# Serial_Gauge_V0_1.net
KiCad netlist of a schematic drawn in EAGLE
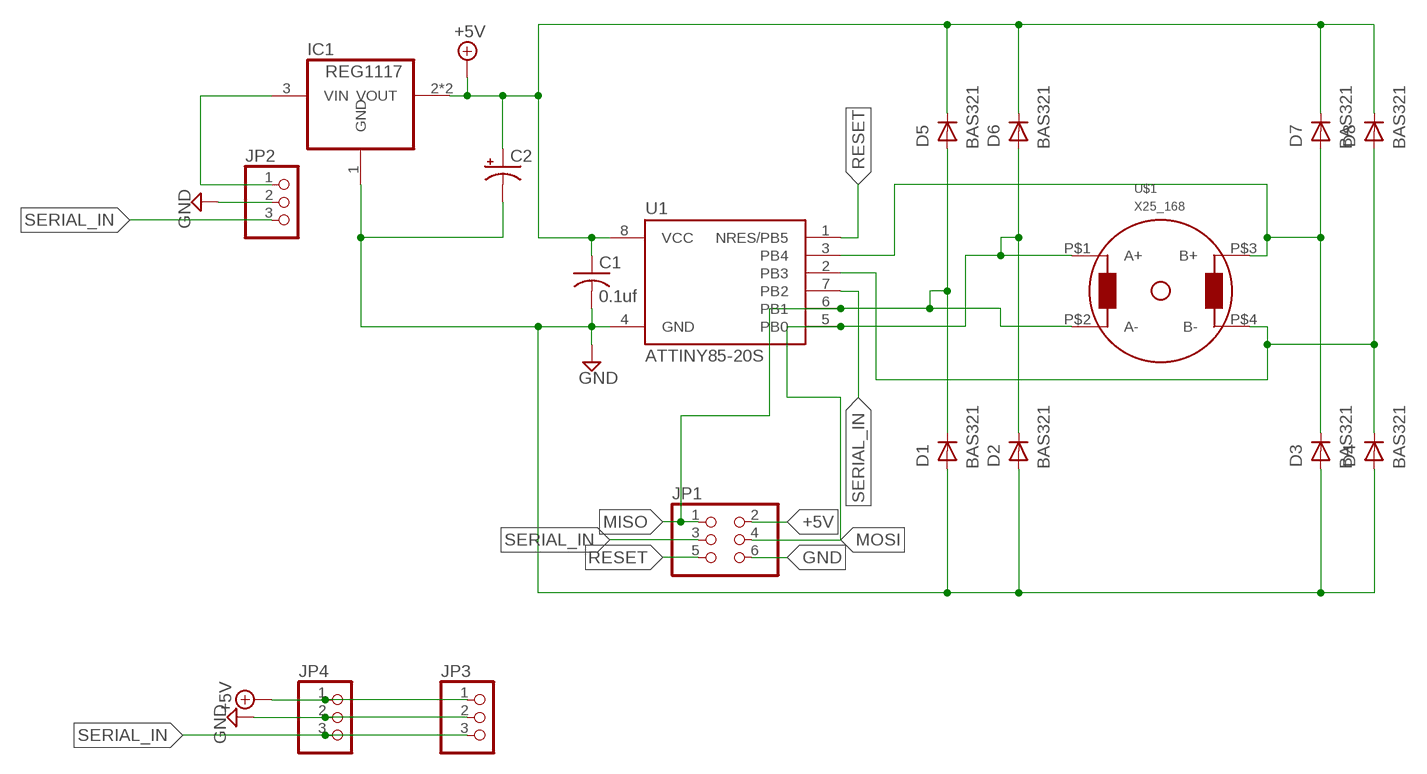
[diagram p0: schematic, sheet 1]

(export (version "E")
  (design (tool "Eeschema 10.0.6"))
  (components
    (comp (ref "C1")
      (value "0.1uf")
      (footprint "eagle-import:C1206K")
      (libsource (lib "eagle-import") (part "C-USC1206K"))
    )
    (comp (ref "C2")
      (value "CPOL-US140CLH-0810")
      (footprint "eagle-import:140CLH-0810")
      (libsource (lib "eagle-import") (part "CPOL-US140CLH-0810"))
    )
    (comp (ref "D1")
      (value "BAS321")
      (footprint "eagle-import:SOD323(F)")
      (libsource (lib "eagle-import") (part "BAS321"))
    )
    (comp (ref "D2")
      (value "BAS321")
      (footprint "eagle-import:SOD323(F)")
      (libsource (lib "eagle-import") (part "BAS321"))
    )
    (comp (ref "D3")
      (value "BAS321")
      (footprint "eagle-import:SOD323(F)")
      (libsource (lib "eagle-import") (part "BAS321"))
    )
    (comp (ref "D4")
      (value "BAS321")
      (footprint "eagle-import:SOD323(F)")
      (libsource (lib "eagle-import") (part "BAS321"))
    )
    (comp (ref "D5")
      (value "BAS321")
      (footprint "eagle-import:SOD323(F)")
      (libsource (lib "eagle-import") (part "BAS321"))
    )
    (comp (ref "D6")
      (value "BAS321")
      (footprint "eagle-import:SOD323(F)")
      (libsource (lib "eagle-import") (part "BAS321"))
    )
    (comp (ref "D7")
      (value "BAS321")
      (footprint "eagle-import:SOD323(F)")
      (libsource (lib "eagle-import") (part "BAS321"))
    )
    (comp (ref "D8")
      (value "BAS321")
      (footprint "eagle-import:SOD323(F)")
      (libsource (lib "eagle-import") (part "BAS321"))
    )
    (comp (ref "IC1")
      (value "REG1117")
      (footprint "eagle-import:SOT223")
      (libsource (lib "eagle-import") (part "REG1117"))
    )
    (comp (ref "JP1")
      (value "PINHD-2X3")
      (footprint "eagle-import:2X03")
      (libsource (lib "eagle-import") (part "PINHD-2X3"))
    )
    (comp (ref "JP2")
      (value "PINHD-1X3")
      (footprint "eagle-import:1X03")
      (libsource (lib "eagle-import") (part "PINHD-1X3"))
    )
    (comp (ref "JP3")
      (value "PINHD-1X3")
      (footprint "eagle-import:1X03")
      (libsource (lib "eagle-import") (part "PINHD-1X3"))
    )
    (comp (ref "JP4")
      (value "PINHD-1X3")
      (footprint "eagle-import:1X03")
      (libsource (lib "eagle-import") (part "PINHD-1X3"))
    )
    (comp (ref "U$1")
      (value "X25_168")
      (footprint "eagle-import:X25_168")
      (libsource (lib "eagle-import") (part "X25_168"))
    )
    (comp (ref "U1")
      (value "ATTINY85-20S")
      (footprint "eagle-import:SOIC8_EIAJ_208MIL")
      (libsource (lib "eagle-import") (part "ATTINY85S-20"))
    )
  )
  (nets
    (net (code "1") (name "+5V") (class "Default")
      (node (ref "C1") (pin "1") (pinfunction "1_1") (pintype "passive"))
      (node (ref "C2") (pin "+") (pinfunction "+_+") (pintype "passive"))
      (node (ref "D5") (pin "1") (pinfunction "K_1") (pintype "passive"))
      (node (ref "D6") (pin "1") (pinfunction "K_1") (pintype "passive"))
      (node (ref "D7") (pin "1") (pinfunction "K_1") (pintype "passive"))
      (node (ref "D8") (pin "1") (pinfunction "K_1") (pintype "passive"))
      (node (ref "IC1") (pin "2") (pinfunction "VOUT_2") (pintype "output"))
      (node (ref "IC1") (pin "4") (pinfunction "VOUT_4") (pintype "output"))
      (node (ref "JP1") (pin "2") (pinfunction "2_2") (pintype "passive"))
      (node (ref "JP3") (pin "1") (pinfunction "1_1") (pintype "passive"))
      (node (ref "JP4") (pin "1") (pinfunction "1_1") (pintype "passive"))
      (node (ref "U1") (pin "8") (pinfunction "VCC_8") (pintype "power_in"))
    )
    (net (code "2") (name "GND") (class "Default")
      (node (ref "C1") (pin "2") (pinfunction "2_2") (pintype "passive"))
      (node (ref "C2") (pin "-") (pinfunction "-_-") (pintype "passive"))
      (node (ref "D1") (pin "2") (pinfunction "A_2") (pintype "passive"))
      (node (ref "D2") (pin "2") (pinfunction "A_2") (pintype "passive"))
      (node (ref "D3") (pin "2") (pinfunction "A_2") (pintype "passive"))
      (node (ref "D4") (pin "2") (pinfunction "A_2") (pintype "passive"))
      (node (ref "IC1") (pin "1") (pinfunction "GND_1") (pintype "power_in"))
      (node (ref "JP1") (pin "6") (pinfunction "6_6") (pintype "passive"))
      (node (ref "JP2") (pin "2") (pinfunction "2_2") (pintype "passive"))
      (node (ref "JP3") (pin "2") (pinfunction "2_2") (pintype "passive"))
      (node (ref "JP4") (pin "2") (pinfunction "2_2") (pintype "passive"))
      (node (ref "U1") (pin "4") (pinfunction "GND_4") (pintype "power_in"))
    )
    (net (code "3") (name "MISO") (class "Default")
      (node (ref "D1") (pin "1") (pinfunction "K_1") (pintype "passive"))
      (node (ref "D5") (pin "2") (pinfunction "A_2") (pintype "passive"))
      (node (ref "JP1") (pin "1") (pinfunction "1_1") (pintype "passive"))
      (node (ref "U$1") (pin "P$2") (pinfunction "A-_P$2") (pintype "input"))
      (node (ref "U1") (pin "6") (pinfunction "PB1_6") (pintype "bidirectional"))
    )
    (net (code "4") (name "MOSI") (class "Default")
      (node (ref "D2") (pin "1") (pinfunction "K_1") (pintype "passive"))
      (node (ref "D6") (pin "2") (pinfunction "A_2") (pintype "passive"))
      (node (ref "JP1") (pin "4") (pinfunction "4_4") (pintype "passive"))
      (node (ref "U$1") (pin "P$1") (pinfunction "A+_P$1") (pintype "input"))
      (node (ref "U1") (pin "5") (pinfunction "PB0_5") (pintype "bidirectional"))
    )
    (net (code "5") (name "Net-(D3-K)") (class "Default")
      (node (ref "D3") (pin "1") (pinfunction "K_1") (pintype "passive"))
      (node (ref "D7") (pin "2") (pinfunction "A_2") (pintype "passive"))
      (node (ref "U$1") (pin "P$3") (pinfunction "B+_P$3") (pintype "input"))
      (node (ref "U1") (pin "3") (pinfunction "PB4_3") (pintype "bidirectional"))
    )
    (net (code "6") (name "Net-(D4-K)") (class "Default")
      (node (ref "D4") (pin "1") (pinfunction "K_1") (pintype "passive"))
      (node (ref "D8") (pin "2") (pinfunction "A_2") (pintype "passive"))
      (node (ref "U$1") (pin "P$4") (pinfunction "B-_P$4") (pintype "input"))
      (node (ref "U1") (pin "2") (pinfunction "PB3_2") (pintype "bidirectional"))
    )
    (net (code "7") (name "Net-(IC1-VIN)") (class "Default")
      (node (ref "IC1") (pin "3") (pinfunction "VIN_3") (pintype "input"))
      (node (ref "JP2") (pin "1") (pinfunction "1_1") (pintype "passive"))
    )
    (net (code "8") (name "RESET") (class "Default")
      (node (ref "JP1") (pin "5") (pinfunction "5_5") (pintype "passive"))
      (node (ref "U1") (pin "1") (pinfunction "NRES/PB5_1") (pintype "bidirectional"))
    )
    (net (code "9") (name "SERIAL_IN") (class "Default")
      (node (ref "JP1") (pin "3") (pinfunction "3_3") (pintype "passive"))
      (node (ref "JP2") (pin "3") (pinfunction "3_3") (pintype "passive"))
      (node (ref "JP3") (pin "3") (pinfunction "3_3") (pintype "passive"))
      (node (ref "JP4") (pin "3") (pinfunction "3_3") (pintype "passive"))
      (node (ref "U1") (pin "7") (pinfunction "PB2_7") (pintype "bidirectional"))
    )
  )
)
